# power.net
KiCad netlist of a schematic drawn in EAGLE
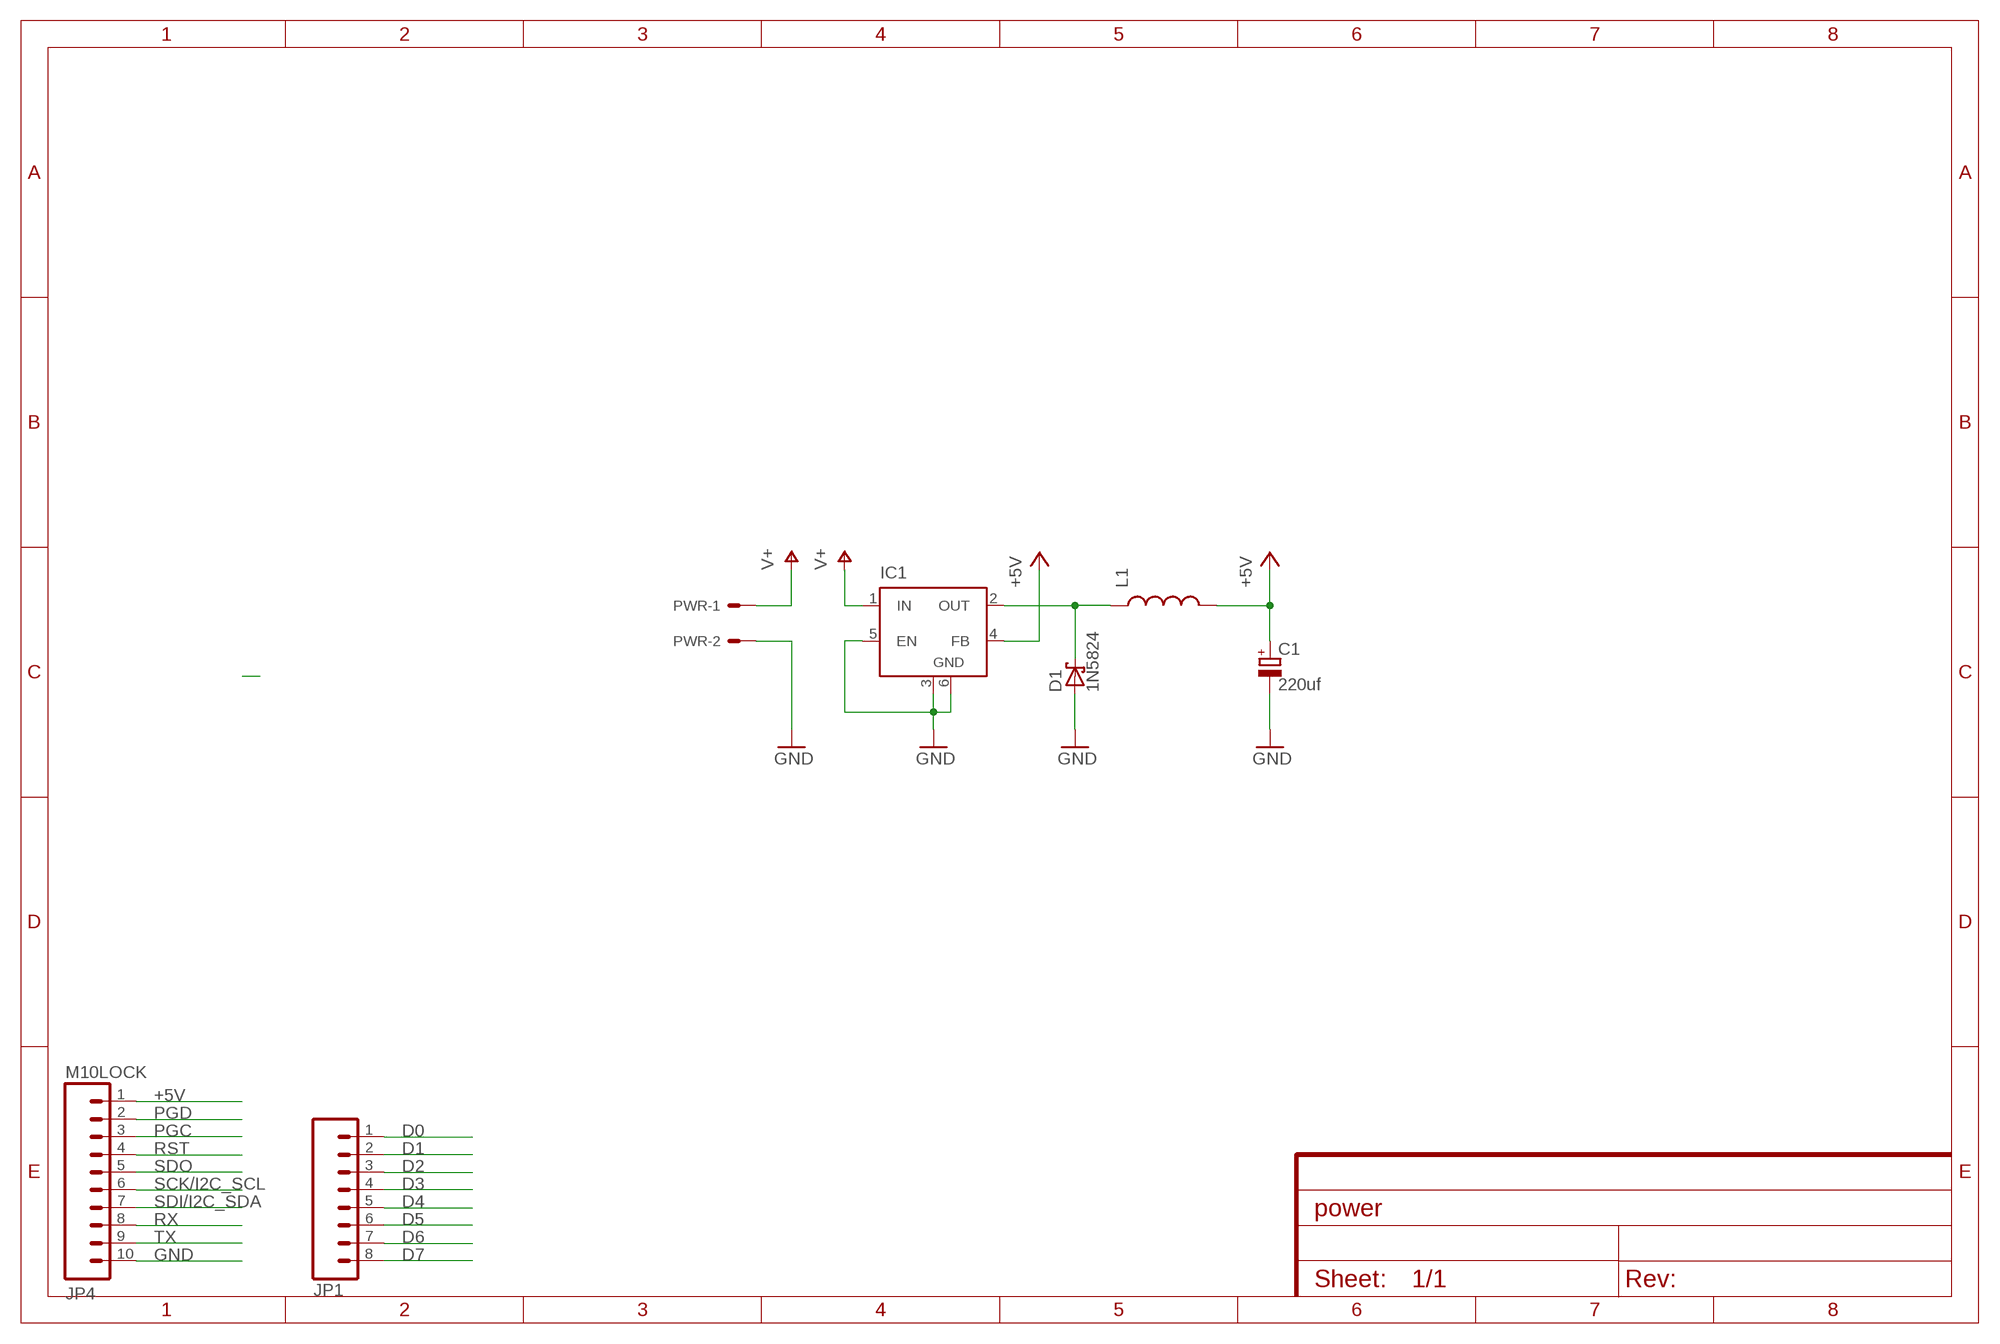
[diagram p0: schematic, sheet 1]

(export (version "E")
  (design (tool "Eeschema 10.0.6"))
  (components
    (comp (ref "C1")
      (value "220uf")
      (footprint "eagle-import:E2,5-6")
      (libsource (lib "eagle-import") (part "CPOL-EUE2.5-6"))
    )
    (comp (ref "D1")
      (value "1N5824")
      (footprint "eagle-import:DO41-7.6")
      (libsource (lib "eagle-import") (part "1N5817-B"))
    )
    (comp (ref "IC1")
      (value "LM2596S")
      (footprint "eagle-import:TO263-5")
      (libsource (lib "eagle-import") (part "LM2596S"))
    )
    (comp (ref "JP1")
      (value "M08LOCK")
      (footprint "eagle-import:1X08_LOCK")
      (libsource (lib "eagle-import") (part "M08LOCK"))
    )
    (comp (ref "JP4")
      (value "M10LOCK")
      (footprint "eagle-import:1X10_LOCK")
      (libsource (lib "eagle-import") (part "M10LOCK"))
    )
    (comp (ref "L1")
      (value "INDUCTORSRU1038")
      (footprint "eagle-import:SRU1038")
      (libsource (lib "eagle-import") (part "INDUCTORSRU1038"))
    )
    (comp (ref "PWR")
      (value "22-05-7028-02")
      (footprint "eagle-import:7395-02")
      (libsource (lib "eagle-import") (part "22-?-0205-7028"))
    )
  )
  (nets
    (net (code "1") (name "+5V") (class "Default")
      (node (ref "C1") (pin "+") (pinfunction "+_+") (pintype "passive"))
      (node (ref "IC1") (pin "4") (pinfunction "FB_4") (pintype "input"))
      (node (ref "JP4") (pin "1") (pinfunction "1_1") (pintype "passive"))
      (node (ref "L1") (pin "2") (pinfunction "2_2") (pintype "passive"))
    )
    (net (code "2") (name "/D0") (class "Default")
      (node (ref "JP1") (pin "1") (pinfunction "1_1") (pintype "passive"))
    )
    (net (code "3") (name "/D1") (class "Default")
      (node (ref "JP1") (pin "2") (pinfunction "2_2") (pintype "passive"))
    )
    (net (code "4") (name "/D2") (class "Default")
      (node (ref "JP1") (pin "3") (pinfunction "3_3") (pintype "passive"))
    )
    (net (code "5") (name "/D3") (class "Default")
      (node (ref "JP1") (pin "4") (pinfunction "4_4") (pintype "passive"))
    )
    (net (code "6") (name "/D4") (class "Default")
      (node (ref "JP1") (pin "5") (pinfunction "5_5") (pintype "passive"))
    )
    (net (code "7") (name "/D5") (class "Default")
      (node (ref "JP1") (pin "6") (pinfunction "6_6") (pintype "passive"))
    )
    (net (code "8") (name "/D6") (class "Default")
      (node (ref "JP1") (pin "7") (pinfunction "7_7") (pintype "passive"))
    )
    (net (code "9") (name "/D7") (class "Default")
      (node (ref "JP1") (pin "8") (pinfunction "8_8") (pintype "passive"))
    )
    (net (code "10") (name "/PGC") (class "Default")
      (node (ref "JP4") (pin "3") (pinfunction "3_3") (pintype "passive"))
    )
    (net (code "11") (name "/PGD") (class "Default")
      (node (ref "JP4") (pin "2") (pinfunction "2_2") (pintype "passive"))
    )
    (net (code "12") (name "/RST") (class "Default")
      (node (ref "JP4") (pin "4") (pinfunction "4_4") (pintype "passive"))
    )
    (net (code "13") (name "/RX") (class "Default")
      (node (ref "JP4") (pin "8") (pinfunction "8_8") (pintype "passive"))
    )
    (net (code "14") (name "/SCK{slash}I2C_SCL") (class "Default")
      (node (ref "JP4") (pin "6") (pinfunction "6_6") (pintype "passive"))
    )
    (net (code "15") (name "/SDI{slash}I2C_SDA") (class "Default")
      (node (ref "JP4") (pin "7") (pinfunction "7_7") (pintype "passive"))
    )
    (net (code "16") (name "/SDO") (class "Default")
      (node (ref "JP4") (pin "5") (pinfunction "5_5") (pintype "passive"))
    )
    (net (code "17") (name "/TX") (class "Default")
      (node (ref "JP4") (pin "9") (pinfunction "9_9") (pintype "passive"))
    )
    (net (code "18") (name "GND") (class "Default")
      (node (ref "C1") (pin "-") (pinfunction "-_-") (pintype "passive"))
      (node (ref "D1") (pin "A") (pinfunction "A_A") (pintype "passive"))
      (node (ref "IC1") (pin "3") (pinfunction "GND_3") (pintype "power_in"))
      (node (ref "IC1") (pin "5") (pinfunction "EN_5") (pintype "input"))
      (node (ref "IC1") (pin "6") (pinfunction "GND_6") (pintype "power_in"))
      (node (ref "JP4") (pin "10") (pinfunction "10_10") (pintype "passive"))
      (node (ref "PWR") (pin "2") (pinfunction "S_2") (pintype "passive"))
    )
    (net (code "19") (name "Net-(IC1-OUT)") (class "Default")
      (node (ref "D1") (pin "C") (pinfunction "C_C") (pintype "passive"))
      (node (ref "IC1") (pin "2") (pinfunction "OUT_2") (pintype "output"))
      (node (ref "L1") (pin "1") (pinfunction "1_1") (pintype "passive"))
    )
    (net (code "20") (name "V+") (class "Default")
      (node (ref "IC1") (pin "1") (pinfunction "IN_1") (pintype "input"))
      (node (ref "PWR") (pin "1") (pinfunction "S_1") (pintype "passive"))
    )
  )
)
